# Power.net
KiCad netlist of a schematic drawn in Altium Designer
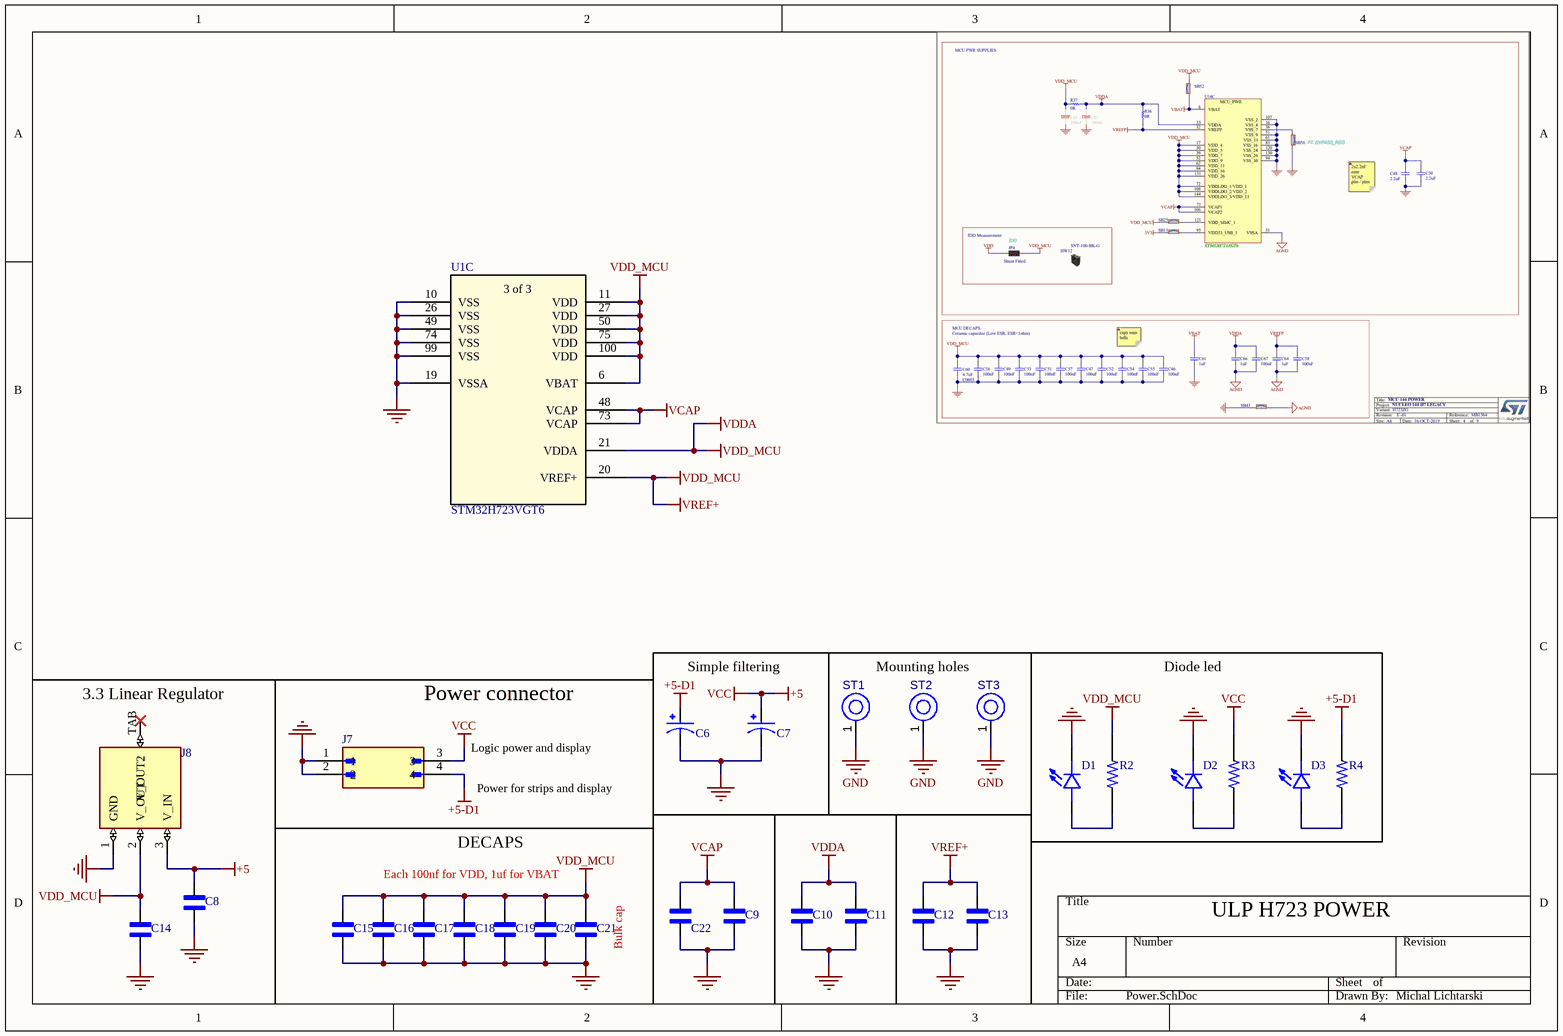
[diagram p0: Power.SchDoc]

(export (version "E")
  (design (tool "Eeschema 10.0.6"))
  (components
    (comp (ref "C6")
      (value "EEEFT1E101AP")
      (footprint "EEE-FT1E101AP:CAP_EEEFT1E101AP")
      (description "10uF 25V")
      (fields (field (name "MF") "{'manufacturer': u'Panasonic Electronic'}"))
      (libsource (lib "*") (part "EEEFT1E101AP"))
    )
    (comp (ref "C7")
      (value "EEEFT1E101AP")
      (footprint "EEE-FT1E101AP:CAP_EEEFT1E101AP")
      (description "10uF 25V")
      (fields (field (name "MF") "{'manufacturer': u'Panasonic Electronic'}"))
      (libsource (lib "*") (part "EEEFT1E101AP"))
    )
    (comp (ref "C8")
      (value "CL10A105KA8NNNC")
      (footprint "CL10A105KA8NNNC:CAPC1608X90N")
      (description "10uf 0603")
      (fields (field (name "MF") "{'manufacturer': u'Samsung Electro-Mechanics'}"))
      (libsource (lib "*") (part "CL10A105KA8NNNC"))
    )
    (comp (ref "C9")
      (value "CL10A225KO8NNNC")
      (footprint "06035C104KAT2A:CAPC1608X90N")
      (description "2,2uf 0603")
      (fields (field (name "MF") "{'manufacturer': u'AVX'}") (field (name "MP") "06035C104KAT2A"))
      (libsource (lib "*") (part "06035C104KAT2A"))
    )
    (comp (ref "C10")
      (value "CL10A105KA8NNNC")
      (footprint "CL10A105KA8NNNC:CAPC1608X90N")
      (description "1uf 0603")
      (fields (field (name "MF") "{'manufacturer': u'Samsung Electro-Mechanics'}"))
      (libsource (lib "*") (part "CL10A105KA8NNNC"))
    )
    (comp (ref "C11")
      (value "06035C104KAT2A")
      (footprint "06035C104KAT2A:CAPC1608X90N")
      (description "100nf 0603")
      (fields (field (name "MF") "{'manufacturer': u'AVX'}"))
      (libsource (lib "*") (part "06035C104KAT2A"))
    )
    (comp (ref "C12")
      (value "CL10A105KA8NNNC")
      (footprint "CL10A105KA8NNNC:CAPC1608X90N")
      (description "1uf 0603")
      (fields (field (name "MF") "{'manufacturer': u'Samsung Electro-Mechanics'}"))
      (libsource (lib "*") (part "CL10A105KA8NNNC"))
    )
    (comp (ref "C13")
      (value "06035C104KAT2A")
      (footprint "06035C104KAT2A:CAPC1608X90N")
      (description "100nf 0603")
      (fields (field (name "MF") "{'manufacturer': u'AVX'}"))
      (libsource (lib "*") (part "06035C104KAT2A"))
    )
    (comp (ref "C14")
      (value "CL10A105KA8NNNC")
      (footprint "CL10A105KA8NNNC:CAPC1608X90N")
      (description "10uf 0603")
      (fields (field (name "MF") "{'manufacturer': u'Samsung Electro-Mechanics'}"))
      (libsource (lib "*") (part "CL10A105KA8NNNC"))
    )
    (comp (ref "C15")
      (value "CL10A105KA8NNNC")
      (footprint "CL10A105KA8NNNC:CAPC1608X90N")
      (description "1uf 0603")
      (fields (field (name "MF") "{'manufacturer': u'Samsung Electro-Mechanics'}"))
      (libsource (lib "*") (part "CL10A105KA8NNNC"))
    )
    (comp (ref "C16")
      (value "06035C104KAT2A")
      (footprint "06035C104KAT2A:CAPC1608X90N")
      (description "100nf 0603")
      (fields (field (name "MF") "{'manufacturer': u'AVX'}"))
      (libsource (lib "*") (part "06035C104KAT2A"))
    )
    (comp (ref "C17")
      (value "06035C104KAT2A")
      (footprint "06035C104KAT2A:CAPC1608X90N")
      (description "100nf 0603")
      (fields (field (name "MF") "{'manufacturer': u'AVX'}"))
      (libsource (lib "*") (part "06035C104KAT2A"))
    )
    (comp (ref "C18")
      (value "06035C104KAT2A")
      (footprint "06035C104KAT2A:CAPC1608X90N")
      (description "100nf 0603")
      (fields (field (name "MF") "{'manufacturer': u'AVX'}"))
      (libsource (lib "*") (part "06035C104KAT2A"))
    )
    (comp (ref "C19")
      (value "06035C104KAT2A")
      (footprint "06035C104KAT2A:CAPC1608X90N")
      (description "100nf 0603")
      (fields (field (name "MF") "{'manufacturer': u'AVX'}"))
      (libsource (lib "*") (part "06035C104KAT2A"))
    )
    (comp (ref "C20")
      (value "06035C104KAT2A")
      (footprint "06035C104KAT2A:CAPC1608X90N")
      (description "100nf 0603")
      (fields (field (name "MF") "{'manufacturer': u'AVX'}"))
      (libsource (lib "*") (part "06035C104KAT2A"))
    )
    (comp (ref "C21")
      (value "CL10A475MA8NQNC")
      (footprint "06035C104KAT2A:CAPC1608X90N")
      (description "4,7uf 0603")
      (fields (field (name "MF") "{'manufacturer': u'AVX'}") (field (name "MP") "06035C104KAT2A"))
      (libsource (lib "*") (part "06035C104KAT2A"))
    )
    (comp (ref "C22")
      (value "CL10A225KO8NNNC")
      (footprint "06035C104KAT2A:CAPC1608X90N")
      (description "2,2uf 0603")
      (fields (field (name "MF") "{'manufacturer': u'AVX'}") (field (name "MP") "06035C104KAT2A"))
      (libsource (lib "") (part "06035C104KAT2A_1"))
    )
    (comp (ref "D1")
      (value "LTST-C190KGKT")
      (footprint "LTST-C190KGKT:LEDC1608X35N")
      (fields (field (name "MF") "{'manufacturer': u'Lite-On Electronics'}"))
      (libsource (lib "*") (part "LTST-C190KGKT"))
    )
    (comp (ref "D2")
      (value "LTST-C191TBKT")
      (footprint "LTST-C190KGKT:LEDC1608X35N")
      (description "0603 blue")
      (fields
        (field (name "MF") "{'manufacturer': u'Lite-On Electronics'}")
        (field (name "MP") "LTST-C190KGKT")
      )
      (libsource (lib "*") (part "LTST-C190KGKT"))
    )
    (comp (ref "D3")
      (value "LTST-C191TBKT")
      (footprint "LTST-C190KGKT:LEDC1608X35N")
      (description "0603 blue")
      (fields
        (field (name "MF") "{'manufacturer': u'Lite-On Electronics'}")
        (field (name "MP") "LTST-C190KGKT")
      )
      (libsource (lib "*") (part "LTST-C190KGKT"))
    )
    (comp (ref "J7")
      (value "353180420")
      (footprint "35318-0420:MOLEX_353180420")
      (description "Connector Header Through Hole, Right Angle 4 position 0.165in (4.20mm)")
      (fields (field (name "MF") "{'manufacturer': u'Molex'}"))
      (libsource (lib "*") (part "353180420"))
    )
    (comp (ref "J8")
      (value "LD1117AS33TR")
      (footprint "SOT223")
      (description "Linear Voltage Regulator 3.3V, 1.15V drop")
      (fields (field (name "MP") "LD1117AS33") (field (name "MF") "STMicroelectronics"))
      (libsource (lib "LD1117AS33") (part "LD1117AS33"))
    )
    (comp (ref "R2")
      (value "RP73PF1J10KBTDF")
      (footprint "RP73PF1J10KBTDF:RESC1608X50N")
      (description "80Ohm 0603")
      (fields (field (name "MF") "{'manufacturer': u'TE Connectivity'}"))
      (libsource (lib "*") (part "RP73PF1J10KBTDF"))
    )
    (comp (ref "R3")
      (value "RP73PF1J10KBTDF")
      (footprint "RP73PF1J10KBTDF:RESC1608X50N")
      (description "20Ohm 0603")
      (fields (field (name "MF") "{'manufacturer': u'TE Connectivity'}"))
      (libsource (lib "*") (part "RP73PF1J10KBTDF"))
    )
    (comp (ref "R4")
      (value "RP73PF1J10KBTDF")
      (footprint "RP73PF1J10KBTDF:RESC1608X50N")
      (description "20Ohm 0603")
      (fields (field (name "MF") "{'manufacturer': u'TE Connectivity'}"))
      (libsource (lib "*") (part "RP73PF1J10KBTDF"))
    )
    (comp (ref "ST1")
      (value "PTH-M2D5X5")
      (footprint "PTH-M2D5X5")
      (description "M2 PTH (2.5mm), 5mm pad")
      (libsource (lib "Michal") (part "CMP-00028-00000-1"))
    )
    (comp (ref "ST2")
      (value "PTH-M2D5X5")
      (footprint "PTH-M2D5X5")
      (description "M2 PTH (2.5mm), 5mm pad")
      (libsource (lib "Michal") (part "CMP-00028-00000-1"))
    )
    (comp (ref "ST3")
      (value "PTH-M2D5X5")
      (footprint "PTH-M2D5X5")
      (description "M2 PTH (2.5mm), 5mm pad")
      (libsource (lib "Michal") (part "CMP-00028-00000-1"))
    )
    (comp (ref "U1")
      (value "STM32H723VGT6")
      (footprint "LQFP100_STM")
      (description "No Description Available")
      (fields (field (name "COPYRIGHT") "Copyright (C) 2023 Ultra Librarian. All rights reserved."))
      (libsource (lib "STM32H723VGT6") (part "STM32H723VGT6"))
    )
  )
  (nets
    (net (code "1") (name "+5") (class "Default")
      (node (ref "C7") (pin "1") (pinfunction "1_1") (pintype "passive"))
      (node (ref "C8") (pin "1") (pinfunction "1_1") (pintype "passive"))
      (node (ref "J7") (pin "3") (pinfunction "3_3") (pintype "passive"))
      (node (ref "J8") (pin "3") (pinfunction "V_IN_3") (pintype "bidirectional"))
      (node (ref "R3") (pin "2") (pinfunction "2_2") (pintype "passive"))
    )
    (net (code "2") (name "+5-D1") (class "Default")
      (node (ref "C6") (pin "1") (pinfunction "1_1") (pintype "passive"))
      (node (ref "J7") (pin "4") (pinfunction "4_4") (pintype "passive"))
      (node (ref "R4") (pin "2") (pinfunction "2_2") (pintype "passive"))
    )
    (net (code "3") (name "GND") (class "Default")
      (node (ref "C10") (pin "2") (pinfunction "2_2") (pintype "passive"))
      (node (ref "C11") (pin "1") (pinfunction "1_1") (pintype "passive"))
      (node (ref "C12") (pin "2") (pinfunction "2_2") (pintype "passive"))
      (node (ref "C13") (pin "1") (pinfunction "1_1") (pintype "passive"))
      (node (ref "C14") (pin "2") (pinfunction "2_2") (pintype "passive"))
      (node (ref "C15") (pin "2") (pinfunction "2_2") (pintype "passive"))
      (node (ref "C16") (pin "1") (pinfunction "1_1") (pintype "passive"))
      (node (ref "C17") (pin "1") (pinfunction "1_1") (pintype "passive"))
      (node (ref "C18") (pin "1") (pinfunction "1_1") (pintype "passive"))
      (node (ref "C19") (pin "1") (pinfunction "1_1") (pintype "passive"))
      (node (ref "C20") (pin "1") (pinfunction "1_1") (pintype "passive"))
      (node (ref "C21") (pin "1") (pinfunction "1_1") (pintype "passive"))
      (node (ref "C22") (pin "2") (pinfunction "2_2") (pintype "passive"))
      (node (ref "C6") (pin "2") (pinfunction "2_2") (pintype "passive"))
      (node (ref "C7") (pin "2") (pinfunction "2_2") (pintype "passive"))
      (node (ref "C8") (pin "2") (pinfunction "2_2") (pintype "passive"))
      (node (ref "C9") (pin "1") (pinfunction "1_1") (pintype "passive"))
      (node (ref "D1") (pin "C") (pinfunction "C_C") (pintype "passive"))
      (node (ref "D2") (pin "C") (pinfunction "C_C") (pintype "passive"))
      (node (ref "D3") (pin "C") (pinfunction "C_C") (pintype "passive"))
      (node (ref "J7") (pin "1") (pinfunction "1_1") (pintype "passive"))
      (node (ref "J7") (pin "2") (pinfunction "2_2") (pintype "passive"))
      (node (ref "J8") (pin "1") (pinfunction "GND_1") (pintype "bidirectional"))
      (node (ref "ST1") (pin "1") (pinfunction "H1_1") (pintype "passive"))
      (node (ref "ST2") (pin "1") (pinfunction "H1_1") (pintype "passive"))
      (node (ref "ST3") (pin "1") (pinfunction "H1_1") (pintype "passive"))
      (node (ref "U1") (pin "10") (pinfunction "VSS_10") (pintype "power_in"))
      (node (ref "U1") (pin "19") (pinfunction "VSSA_19") (pintype "power_in"))
      (node (ref "U1") (pin "26") (pinfunction "VSS_26") (pintype "power_in"))
      (node (ref "U1") (pin "49") (pinfunction "VSS_49") (pintype "power_in"))
      (node (ref "U1") (pin "74") (pinfunction "VSS_74") (pintype "power_in"))
      (node (ref "U1") (pin "99") (pinfunction "VSS_99") (pintype "power_in"))
    )
    (net (code "4") (name "Net-(D1-PadA)") (class "Default")
      (node (ref "D1") (pin "A") (pinfunction "A_A") (pintype "passive"))
      (node (ref "R2") (pin "1") (pinfunction "1_1") (pintype "passive"))
    )
    (net (code "5") (name "Net-(D2-PadA)") (class "Default")
      (node (ref "D2") (pin "A") (pinfunction "A_A") (pintype "passive"))
      (node (ref "R3") (pin "1") (pinfunction "1_1") (pintype "passive"))
    )
    (net (code "6") (name "Net-(D3-PadA)") (class "Default")
      (node (ref "D3") (pin "A") (pinfunction "A_A") (pintype "passive"))
      (node (ref "R4") (pin "1") (pinfunction "1_1") (pintype "passive"))
    )
    (net (code "7") (name "VCAP") (class "Default")
      (node (ref "C22") (pin "1") (pinfunction "1_1") (pintype "passive"))
      (node (ref "C9") (pin "2") (pinfunction "2_2") (pintype "passive"))
      (node (ref "U1") (pin "48") (pinfunction "VCAP_48") (pintype "power_in"))
      (node (ref "U1") (pin "73") (pinfunction "VCAP_73") (pintype "power_in"))
    )
    (net (code "8") (name "VDDA") (class "Default")
      (node (ref "C10") (pin "1") (pinfunction "1_1") (pintype "passive"))
      (node (ref "C11") (pin "2") (pinfunction "2_2") (pintype "passive"))
      (node (ref "C12") (pin "1") (pinfunction "1_1") (pintype "passive"))
      (node (ref "C13") (pin "2") (pinfunction "2_2") (pintype "passive"))
      (node (ref "C14") (pin "1") (pinfunction "1_1") (pintype "passive"))
      (node (ref "C15") (pin "1") (pinfunction "1_1") (pintype "passive"))
      (node (ref "C16") (pin "2") (pinfunction "2_2") (pintype "passive"))
      (node (ref "C17") (pin "2") (pinfunction "2_2") (pintype "passive"))
      (node (ref "C18") (pin "2") (pinfunction "2_2") (pintype "passive"))
      (node (ref "C19") (pin "2") (pinfunction "2_2") (pintype "passive"))
      (node (ref "C20") (pin "2") (pinfunction "2_2") (pintype "passive"))
      (node (ref "C21") (pin "2") (pinfunction "2_2") (pintype "passive"))
      (node (ref "J8") (pin "2") (pinfunction "V_OUT_2") (pintype "bidirectional"))
      (node (ref "R2") (pin "2") (pinfunction "2_2") (pintype "passive"))
      (node (ref "U1") (pin "100") (pinfunction "VDD_100") (pintype "power_in"))
      (node (ref "U1") (pin "11") (pinfunction "VDD_11") (pintype "power_in"))
      (node (ref "U1") (pin "20") (pinfunction "VREF+_20") (pintype "power_in"))
      (node (ref "U1") (pin "21") (pinfunction "VDDA_21") (pintype "power_in"))
      (node (ref "U1") (pin "27") (pinfunction "VDD_27") (pintype "power_in"))
      (node (ref "U1") (pin "50") (pinfunction "VDD_50") (pintype "power_in"))
      (node (ref "U1") (pin "6") (pinfunction "VBAT_6") (pintype "power_in"))
      (node (ref "U1") (pin "75") (pinfunction "VDD_75") (pintype "power_in"))
    )
    (net (code "9") (name "unconnected-(J8-V_OUT2-PadTAB)") (class "Default")
      (node (ref "J8") (pin "TAB") (pinfunction "V_OUT2_TAB") (pintype "bidirectional+no_connect"))
    )
  )
)
